# Power_-_3V3.net
KiCad netlist of a schematic drawn in Altium Designer
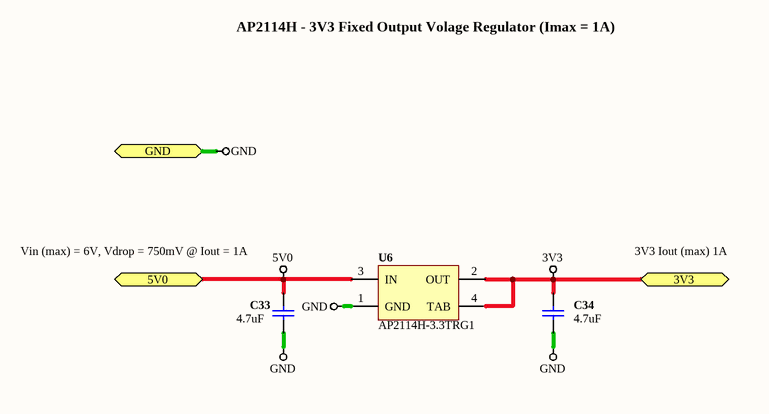
[diagram p0: Power - 3V3.SchDoc]

(export (version "E")
  (design (tool "Eeschema 10.0.6"))
  (components
    (comp (ref "C33")
      (value "4.7uF")
      (footprint "CAPC0603(1608)55_L")
      (fields
        (field (name "TOLERANCE") "±10%")
        (field (name "MANUFACTURER PART NUMBER") "CC0603KRX5R6BB475")
        (field (name "Comment") "CAP 4.7uF 10V 0603(1608)")
      )
      (libsource (lib "Component_Database") (part "CAP_NP"))
    )
    (comp (ref "C34")
      (value "4.7uF")
      (footprint "CAPC0603(1608)55_L")
      (fields
        (field (name "TOLERANCE") "±10%")
        (field (name "MANUFACTURER PART NUMBER") "CC0603KRX5R6BB475")
        (field (name "Comment") "CAP 4.7uF 10V 0603(1608)")
      )
      (libsource (lib "Component_Database") (part "CAP_NP"))
    )
    (comp (ref "U6")
      (value "AP2114H-3.3TRG1")
      (footprint "SOT230P700X180-4L")
      (description "AP2114, 1A Low Dropout Positive Fixed 3V3 Regulator")
      (libsource (lib "AP2114H-3.3TRG1") (part "AP2114H-3.3TRG1"))
    )
  )
  (nets
    (net (code "1") (name "3V3") (class "Default")
      (node (ref "C34") (pin "1") (pinfunction "1_1") (pintype "passive"))
      (node (ref "U6") (pin "2") (pinfunction "OUT_2") (pintype "power_in"))
      (node (ref "U6") (pin "4") (pinfunction "TAB_4") (pintype "power_in"))
    )
    (net (code "2") (name "5V0") (class "Default")
      (node (ref "C33") (pin "1") (pinfunction "1_1") (pintype "passive"))
      (node (ref "U6") (pin "3") (pinfunction "IN_3") (pintype "power_in"))
    )
    (net (code "3") (name "GND") (class "Default")
      (node (ref "C33") (pin "2") (pinfunction "2_2") (pintype "passive"))
      (node (ref "C34") (pin "2") (pinfunction "2_2") (pintype "passive"))
      (node (ref "U6") (pin "1") (pinfunction "GND_1") (pintype "power_in"))
    )
  )
)
